# PLT-01-RevC.net
KiCad netlist of a schematic drawn in EAGLE
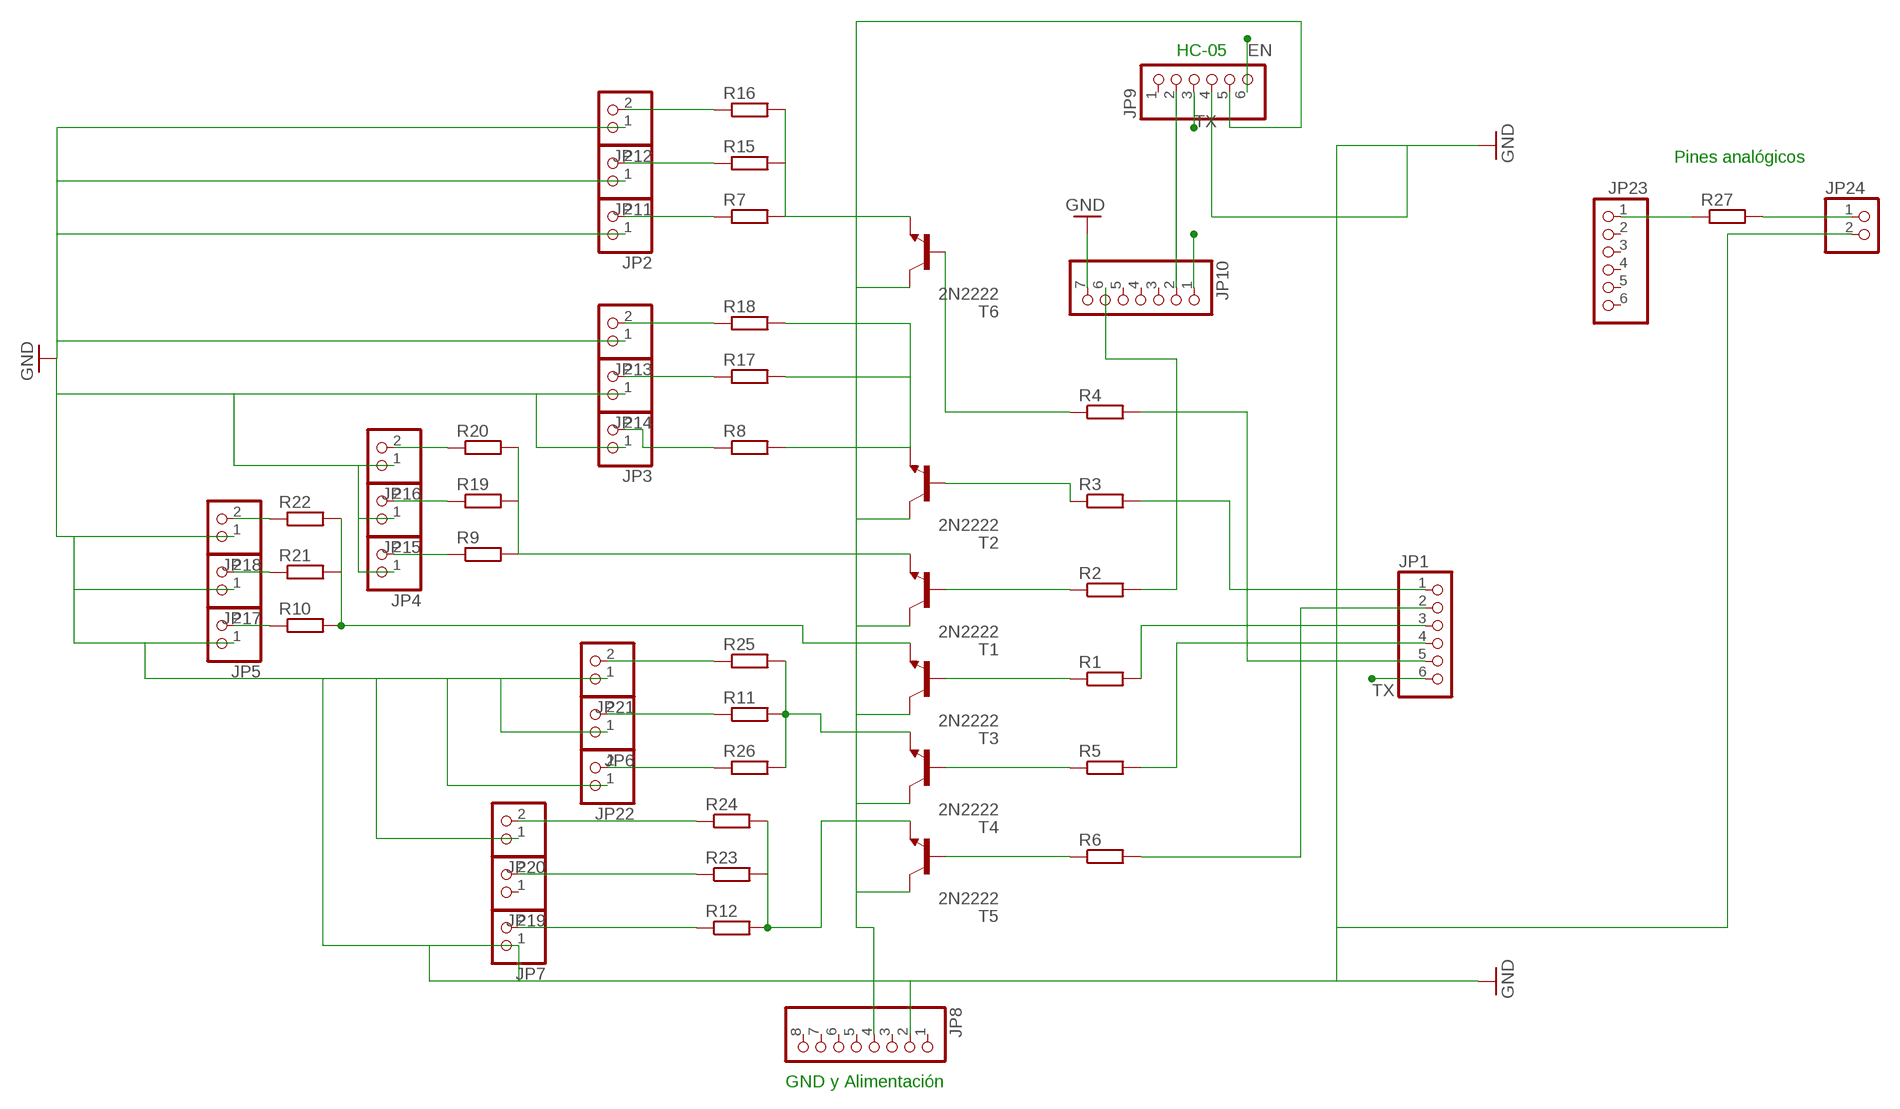
[diagram p0: schematic, sheet 1]

(export (version "E")
  (design (tool "Eeschema 10.0.6"))
  (components
    (comp (ref "JP1")
      (value "PINHD-1X6")
      (footprint "eagle-import:1X06")
      (libsource (lib "eagle-import") (part "PINHD-1X6"))
    )
    (comp (ref "JP2")
      (value "PINHD-1X2")
      (footprint "eagle-import:1X02")
      (libsource (lib "eagle-import") (part "PINHD-1X2"))
    )
    (comp (ref "JP3")
      (value "PINHD-1X2")
      (footprint "eagle-import:1X02")
      (libsource (lib "eagle-import") (part "PINHD-1X2"))
    )
    (comp (ref "JP4")
      (value "PINHD-1X2")
      (footprint "eagle-import:1X02")
      (libsource (lib "eagle-import") (part "PINHD-1X2"))
    )
    (comp (ref "JP5")
      (value "PINHD-1X2")
      (footprint "eagle-import:1X02")
      (libsource (lib "eagle-import") (part "PINHD-1X2"))
    )
    (comp (ref "JP6")
      (value "PINHD-1X2")
      (footprint "eagle-import:1X02")
      (libsource (lib "eagle-import") (part "PINHD-1X2"))
    )
    (comp (ref "JP7")
      (value "PINHD-1X2")
      (footprint "eagle-import:1X02")
      (libsource (lib "eagle-import") (part "PINHD-1X2"))
    )
    (comp (ref "JP8")
      (value "PINHD-1X8")
      (footprint "eagle-import:1X08")
      (libsource (lib "eagle-import") (part "PINHD-1X8"))
    )
    (comp (ref "JP9")
      (value "PINHD-1X6")
      (footprint "eagle-import:1X06")
      (libsource (lib "eagle-import") (part "PINHD-1X6"))
    )
    (comp (ref "JP10")
      (value "PINHD-1X7")
      (footprint "eagle-import:1X07")
      (libsource (lib "eagle-import") (part "PINHD-1X7"))
    )
    (comp (ref "JP11")
      (value "PINHD-1X2")
      (footprint "eagle-import:1X02")
      (libsource (lib "eagle-import") (part "PINHD-1X2"))
    )
    (comp (ref "JP12")
      (value "PINHD-1X2")
      (footprint "eagle-import:1X02")
      (libsource (lib "eagle-import") (part "PINHD-1X2"))
    )
    (comp (ref "JP13")
      (value "PINHD-1X2")
      (footprint "eagle-import:1X02")
      (libsource (lib "eagle-import") (part "PINHD-1X2"))
    )
    (comp (ref "JP14")
      (value "PINHD-1X2")
      (footprint "eagle-import:1X02")
      (libsource (lib "eagle-import") (part "PINHD-1X2"))
    )
    (comp (ref "JP15")
      (value "PINHD-1X2")
      (footprint "eagle-import:1X02")
      (libsource (lib "eagle-import") (part "PINHD-1X2"))
    )
    (comp (ref "JP16")
      (value "PINHD-1X2")
      (footprint "eagle-import:1X02")
      (libsource (lib "eagle-import") (part "PINHD-1X2"))
    )
    (comp (ref "JP17")
      (value "PINHD-1X2")
      (footprint "eagle-import:1X02")
      (libsource (lib "eagle-import") (part "PINHD-1X2"))
    )
    (comp (ref "JP18")
      (value "PINHD-1X2")
      (footprint "eagle-import:1X02")
      (libsource (lib "eagle-import") (part "PINHD-1X2"))
    )
    (comp (ref "JP19")
      (value "PINHD-1X2")
      (footprint "eagle-import:1X02")
      (libsource (lib "eagle-import") (part "PINHD-1X2"))
    )
    (comp (ref "JP20")
      (value "PINHD-1X2")
      (footprint "eagle-import:1X02")
      (libsource (lib "eagle-import") (part "PINHD-1X2"))
    )
    (comp (ref "JP21")
      (value "PINHD-1X2")
      (footprint "eagle-import:1X02")
      (libsource (lib "eagle-import") (part "PINHD-1X2"))
    )
    (comp (ref "JP22")
      (value "PINHD-1X2")
      (footprint "eagle-import:1X02")
      (libsource (lib "eagle-import") (part "PINHD-1X2"))
    )
    (comp (ref "JP23")
      (value "PINHD-1X6")
      (footprint "eagle-import:1X06")
      (libsource (lib "eagle-import") (part "PINHD-1X6"))
    )
    (comp (ref "JP24")
      (value "PINHD-1X2")
      (footprint "eagle-import:1X02")
      (libsource (lib "eagle-import") (part "PINHD-1X2"))
    )
    (comp (ref "R1")
      (value "R-EU_0207/10")
      (footprint "eagle-import:0207_10")
      (libsource (lib "eagle-import") (part "R-EU_0207/10"))
    )
    (comp (ref "R2")
      (value "R-EU_0207/10")
      (footprint "eagle-import:0207_10")
      (libsource (lib "eagle-import") (part "R-EU_0207/10"))
    )
    (comp (ref "R3")
      (value "R-EU_0207/10")
      (footprint "eagle-import:0207_10")
      (libsource (lib "eagle-import") (part "R-EU_0207/10"))
    )
    (comp (ref "R4")
      (value "R-EU_0207/10")
      (footprint "eagle-import:0207_10")
      (libsource (lib "eagle-import") (part "R-EU_0207/10"))
    )
    (comp (ref "R5")
      (value "R-EU_0207/10")
      (footprint "eagle-import:0207_10")
      (libsource (lib "eagle-import") (part "R-EU_0207/10"))
    )
    (comp (ref "R6")
      (value "R-EU_0207/10")
      (footprint "eagle-import:0207_10")
      (libsource (lib "eagle-import") (part "R-EU_0207/10"))
    )
    (comp (ref "R7")
      (value "R-EU_0207/10")
      (footprint "eagle-import:0207_10")
      (libsource (lib "eagle-import") (part "R-EU_0207/10"))
    )
    (comp (ref "R8")
      (value "R-EU_0207/10")
      (footprint "eagle-import:0207_10")
      (libsource (lib "eagle-import") (part "R-EU_0207/10"))
    )
    (comp (ref "R9")
      (value "R-EU_0207/10")
      (footprint "eagle-import:0207_10")
      (libsource (lib "eagle-import") (part "R-EU_0207/10"))
    )
    (comp (ref "R10")
      (value "R-EU_0207/10")
      (footprint "eagle-import:0207_10")
      (libsource (lib "eagle-import") (part "R-EU_0207/10"))
    )
    (comp (ref "R11")
      (value "R-EU_0207/10")
      (footprint "eagle-import:0207_10")
      (libsource (lib "eagle-import") (part "R-EU_0207/10"))
    )
    (comp (ref "R12")
      (value "R-EU_0207/10")
      (footprint "eagle-import:0207_10")
      (libsource (lib "eagle-import") (part "R-EU_0207/10"))
    )
    (comp (ref "R15")
      (value "R-EU_0207/10")
      (footprint "eagle-import:0207_10")
      (libsource (lib "eagle-import") (part "R-EU_0207/10"))
    )
    (comp (ref "R16")
      (value "R-EU_0207/10")
      (footprint "eagle-import:0207_10")
      (libsource (lib "eagle-import") (part "R-EU_0207/10"))
    )
    (comp (ref "R17")
      (value "R-EU_0207/10")
      (footprint "eagle-import:0207_10")
      (libsource (lib "eagle-import") (part "R-EU_0207/10"))
    )
    (comp (ref "R18")
      (value "R-EU_0207/10")
      (footprint "eagle-import:0207_10")
      (libsource (lib "eagle-import") (part "R-EU_0207/10"))
    )
    (comp (ref "R19")
      (value "R-EU_0207/10")
      (footprint "eagle-import:0207_10")
      (libsource (lib "eagle-import") (part "R-EU_0207/10"))
    )
    (comp (ref "R20")
      (value "R-EU_0207/10")
      (footprint "eagle-import:0207_10")
      (libsource (lib "eagle-import") (part "R-EU_0207/10"))
    )
    (comp (ref "R21")
      (value "R-EU_0207/10")
      (footprint "eagle-import:0207_10")
      (libsource (lib "eagle-import") (part "R-EU_0207/10"))
    )
    (comp (ref "R22")
      (value "R-EU_0207/10")
      (footprint "eagle-import:0207_10")
      (libsource (lib "eagle-import") (part "R-EU_0207/10"))
    )
    (comp (ref "R23")
      (value "R-EU_0207/10")
      (footprint "eagle-import:0207_10")
      (libsource (lib "eagle-import") (part "R-EU_0207/10"))
    )
    (comp (ref "R24")
      (value "R-EU_0207/10")
      (footprint "eagle-import:0207_10")
      (libsource (lib "eagle-import") (part "R-EU_0207/10"))
    )
    (comp (ref "R25")
      (value "R-EU_0207/10")
      (footprint "eagle-import:0207_10")
      (libsource (lib "eagle-import") (part "R-EU_0207/10"))
    )
    (comp (ref "R26")
      (value "R-EU_0207/10")
      (footprint "eagle-import:0207_10")
      (libsource (lib "eagle-import") (part "R-EU_0207/10"))
    )
    (comp (ref "R27")
      (value "R-EU_0207/10")
      (footprint "eagle-import:0207_10")
      (libsource (lib "eagle-import") (part "R-EU_0207/10"))
    )
    (comp (ref "T1")
      (value "2N2222")
      (footprint "eagle-import:TO92-EBC-OVAL")
      (libsource (lib "eagle-import") (part "2N2222"))
    )
    (comp (ref "T2")
      (value "2N2222")
      (footprint "eagle-import:TO92-EBC-OVAL")
      (libsource (lib "eagle-import") (part "2N2222"))
    )
    (comp (ref "T3")
      (value "2N2222")
      (footprint "eagle-import:TO92-EBC-OVAL")
      (libsource (lib "eagle-import") (part "2N2222"))
    )
    (comp (ref "T4")
      (value "2N2222")
      (footprint "eagle-import:TO92-EBC-OVAL")
      (libsource (lib "eagle-import") (part "2N2222"))
    )
    (comp (ref "T5")
      (value "2N2222")
      (footprint "eagle-import:TO92-EBC-OVAL")
      (libsource (lib "eagle-import") (part "2N2222"))
    )
    (comp (ref "T6")
      (value "2N2222")
      (footprint "eagle-import:TO92-EBC-OVAL")
      (libsource (lib "eagle-import") (part "2N2222"))
    )
  )
  (nets
    (net (code "1") (name "/EN") (class "Default")
      (node (ref "JP10") (pin "1") (pinfunction "1_1") (pintype "passive"))
      (node (ref "JP9") (pin "6") (pinfunction "6_6") (pintype "passive"))
    )
    (net (code "2") (name "/TX") (class "Default")
      (node (ref "JP1") (pin "6") (pinfunction "6_6") (pintype "passive"))
      (node (ref "JP9") (pin "3") (pinfunction "3_3") (pintype "passive"))
    )
    (net (code "3") (name "GND") (class "Default")
      (node (ref "JP10") (pin "7") (pinfunction "7_7") (pintype "passive"))
      (node (ref "JP11") (pin "1") (pinfunction "1_1") (pintype "passive"))
      (node (ref "JP12") (pin "1") (pinfunction "1_1") (pintype "passive"))
      (node (ref "JP13") (pin "1") (pinfunction "1_1") (pintype "passive"))
      (node (ref "JP14") (pin "1") (pinfunction "1_1") (pintype "passive"))
      (node (ref "JP15") (pin "1") (pinfunction "1_1") (pintype "passive"))
      (node (ref "JP16") (pin "1") (pinfunction "1_1") (pintype "passive"))
      (node (ref "JP17") (pin "1") (pinfunction "1_1") (pintype "passive"))
      (node (ref "JP18") (pin "1") (pinfunction "1_1") (pintype "passive"))
      (node (ref "JP2") (pin "1") (pinfunction "1_1") (pintype "passive"))
      (node (ref "JP20") (pin "1") (pinfunction "1_1") (pintype "passive"))
      (node (ref "JP21") (pin "1") (pinfunction "1_1") (pintype "passive"))
      (node (ref "JP22") (pin "1") (pinfunction "1_1") (pintype "passive"))
      (node (ref "JP24") (pin "2") (pinfunction "2_2") (pintype "passive"))
      (node (ref "JP3") (pin "1") (pinfunction "1_1") (pintype "passive"))
      (node (ref "JP4") (pin "1") (pinfunction "1_1") (pintype "passive"))
      (node (ref "JP5") (pin "1") (pinfunction "1_1") (pintype "passive"))
      (node (ref "JP6") (pin "1") (pinfunction "1_1") (pintype "passive"))
      (node (ref "JP7") (pin "1") (pinfunction "1_1") (pintype "passive"))
      (node (ref "JP8") (pin "2") (pinfunction "2_2") (pintype "passive"))
      (node (ref "JP9") (pin "4") (pinfunction "4_4") (pintype "passive"))
    )
    (net (code "4") (name "Net-(JP1-Pad1)") (class "Default")
      (node (ref "JP1") (pin "1") (pinfunction "1_1") (pintype "passive"))
      (node (ref "R3") (pin "2") (pinfunction "2_2") (pintype "passive"))
    )
    (net (code "5") (name "Net-(JP1-Pad2)") (class "Default")
      (node (ref "JP1") (pin "2") (pinfunction "2_2") (pintype "passive"))
      (node (ref "R6") (pin "2") (pinfunction "2_2") (pintype "passive"))
    )
    (net (code "6") (name "Net-(JP1-Pad3)") (class "Default")
      (node (ref "JP1") (pin "3") (pinfunction "3_3") (pintype "passive"))
      (node (ref "R1") (pin "2") (pinfunction "2_2") (pintype "passive"))
    )
    (net (code "7") (name "Net-(JP1-Pad4)") (class "Default")
      (node (ref "JP1") (pin "4") (pinfunction "4_4") (pintype "passive"))
      (node (ref "R5") (pin "2") (pinfunction "2_2") (pintype "passive"))
    )
    (net (code "8") (name "Net-(JP1-Pad5)") (class "Default")
      (node (ref "JP1") (pin "5") (pinfunction "5_5") (pintype "passive"))
      (node (ref "R4") (pin "2") (pinfunction "2_2") (pintype "passive"))
    )
    (net (code "9") (name "Net-(JP2-Pad2)") (class "Default")
      (node (ref "JP2") (pin "2") (pinfunction "2_2") (pintype "passive"))
      (node (ref "R7") (pin "1") (pinfunction "1_1") (pintype "passive"))
    )
    (net (code "10") (name "Net-(JP3-Pad2)") (class "Default")
      (node (ref "JP3") (pin "2") (pinfunction "2_2") (pintype "passive"))
      (node (ref "R8") (pin "1") (pinfunction "1_1") (pintype "passive"))
    )
    (net (code "11") (name "Net-(JP4-Pad2)") (class "Default")
      (node (ref "JP4") (pin "2") (pinfunction "2_2") (pintype "passive"))
      (node (ref "R9") (pin "1") (pinfunction "1_1") (pintype "passive"))
    )
    (net (code "12") (name "Net-(JP5-Pad2)") (class "Default")
      (node (ref "JP5") (pin "2") (pinfunction "2_2") (pintype "passive"))
      (node (ref "R10") (pin "1") (pinfunction "1_1") (pintype "passive"))
    )
    (net (code "13") (name "Net-(JP6-Pad2)") (class "Default")
      (node (ref "JP6") (pin "2") (pinfunction "2_2") (pintype "passive"))
      (node (ref "R11") (pin "1") (pinfunction "1_1") (pintype "passive"))
    )
    (net (code "14") (name "Net-(JP7-Pad2)") (class "Default")
      (node (ref "JP7") (pin "2") (pinfunction "2_2") (pintype "passive"))
      (node (ref "R12") (pin "1") (pinfunction "1_1") (pintype "passive"))
    )
    (net (code "15") (name "Net-(JP8-Pad4)") (class "Default")
      (node (ref "JP8") (pin "4") (pinfunction "4_4") (pintype "passive"))
      (node (ref "JP9") (pin "5") (pinfunction "5_5") (pintype "passive"))
      (node (ref "T1") (pin "C") (pinfunction "C_C") (pintype "passive"))
      (node (ref "T2") (pin "C") (pinfunction "C_C") (pintype "passive"))
      (node (ref "T3") (pin "C") (pinfunction "C_C") (pintype "passive"))
      (node (ref "T4") (pin "C") (pinfunction "C_C") (pintype "passive"))
      (node (ref "T5") (pin "C") (pinfunction "C_C") (pintype "passive"))
      (node (ref "T6") (pin "C") (pinfunction "C_C") (pintype "passive"))
    )
    (net (code "16") (name "Net-(JP10-Pad2)") (class "Default")
      (node (ref "JP10") (pin "2") (pinfunction "2_2") (pintype "passive"))
      (node (ref "JP9") (pin "2") (pinfunction "2_2") (pintype "passive"))
    )
    (net (code "17") (name "Net-(JP10-Pad6)") (class "Default")
      (node (ref "JP10") (pin "6") (pinfunction "6_6") (pintype "passive"))
      (node (ref "R2") (pin "2") (pinfunction "2_2") (pintype "passive"))
    )
    (net (code "18") (name "Net-(JP11-Pad2)") (class "Default")
      (node (ref "JP11") (pin "2") (pinfunction "2_2") (pintype "passive"))
      (node (ref "R15") (pin "1") (pinfunction "1_1") (pintype "passive"))
    )
    (net (code "19") (name "Net-(JP12-Pad2)") (class "Default")
      (node (ref "JP12") (pin "2") (pinfunction "2_2") (pintype "passive"))
      (node (ref "R16") (pin "1") (pinfunction "1_1") (pintype "passive"))
    )
    (net (code "20") (name "Net-(JP13-Pad2)") (class "Default")
      (node (ref "JP13") (pin "2") (pinfunction "2_2") (pintype "passive"))
      (node (ref "R18") (pin "1") (pinfunction "1_1") (pintype "passive"))
    )
    (net (code "21") (name "Net-(JP14-Pad2)") (class "Default")
      (node (ref "JP14") (pin "2") (pinfunction "2_2") (pintype "passive"))
      (node (ref "R17") (pin "1") (pinfunction "1_1") (pintype "passive"))
    )
    (net (code "22") (name "Net-(JP15-Pad2)") (class "Default")
      (node (ref "JP15") (pin "2") (pinfunction "2_2") (pintype "passive"))
      (node (ref "R19") (pin "1") (pinfunction "1_1") (pintype "passive"))
    )
    (net (code "23") (name "Net-(JP16-Pad2)") (class "Default")
      (node (ref "JP16") (pin "2") (pinfunction "2_2") (pintype "passive"))
      (node (ref "R20") (pin "1") (pinfunction "1_1") (pintype "passive"))
    )
    (net (code "24") (name "Net-(JP17-Pad2)") (class "Default")
      (node (ref "JP17") (pin "2") (pinfunction "2_2") (pintype "passive"))
      (node (ref "R21") (pin "1") (pinfunction "1_1") (pintype "passive"))
    )
    (net (code "25") (name "Net-(JP18-Pad2)") (class "Default")
      (node (ref "JP18") (pin "2") (pinfunction "2_2") (pintype "passive"))
      (node (ref "R22") (pin "1") (pinfunction "1_1") (pintype "passive"))
    )
    (net (code "26") (name "Net-(JP19-Pad2)") (class "Default")
      (node (ref "JP19") (pin "2") (pinfunction "2_2") (pintype "passive"))
      (node (ref "R23") (pin "1") (pinfunction "1_1") (pintype "passive"))
    )
    (net (code "27") (name "Net-(JP20-Pad2)") (class "Default")
      (node (ref "JP20") (pin "2") (pinfunction "2_2") (pintype "passive"))
      (node (ref "R24") (pin "1") (pinfunction "1_1") (pintype "passive"))
    )
    (net (code "28") (name "Net-(JP21-Pad2)") (class "Default")
      (node (ref "JP21") (pin "2") (pinfunction "2_2") (pintype "passive"))
      (node (ref "R25") (pin "1") (pinfunction "1_1") (pintype "passive"))
    )
    (net (code "29") (name "Net-(JP22-Pad2)") (class "Default")
      (node (ref "JP22") (pin "2") (pinfunction "2_2") (pintype "passive"))
      (node (ref "R26") (pin "1") (pinfunction "1_1") (pintype "passive"))
    )
    (net (code "30") (name "Net-(JP23-Pad1)") (class "Default")
      (node (ref "JP23") (pin "1") (pinfunction "1_1") (pintype "passive"))
      (node (ref "R27") (pin "1") (pinfunction "1_1") (pintype "passive"))
    )
    (net (code "31") (name "Net-(JP24-Pad1)") (class "Default")
      (node (ref "JP24") (pin "1") (pinfunction "1_1") (pintype "passive"))
      (node (ref "R27") (pin "2") (pinfunction "2_2") (pintype "passive"))
    )
    (net (code "32") (name "Net-(R1-Pad1)") (class "Default")
      (node (ref "R1") (pin "1") (pinfunction "1_1") (pintype "passive"))
      (node (ref "T3") (pin "B") (pinfunction "B_B") (pintype "passive"))
    )
    (net (code "33") (name "Net-(R2-Pad1)") (class "Default")
      (node (ref "R2") (pin "1") (pinfunction "1_1") (pintype "passive"))
      (node (ref "T1") (pin "B") (pinfunction "B_B") (pintype "passive"))
    )
    (net (code "34") (name "Net-(R3-Pad1)") (class "Default")
      (node (ref "R3") (pin "1") (pinfunction "1_1") (pintype "passive"))
      (node (ref "T2") (pin "B") (pinfunction "B_B") (pintype "passive"))
    )
    (net (code "35") (name "Net-(R4-Pad1)") (class "Default")
      (node (ref "R4") (pin "1") (pinfunction "1_1") (pintype "passive"))
      (node (ref "T6") (pin "B") (pinfunction "B_B") (pintype "passive"))
    )
    (net (code "36") (name "Net-(R5-Pad1)") (class "Default")
      (node (ref "R5") (pin "1") (pinfunction "1_1") (pintype "passive"))
      (node (ref "T4") (pin "B") (pinfunction "B_B") (pintype "passive"))
    )
    (net (code "37") (name "Net-(R6-Pad1)") (class "Default")
      (node (ref "R6") (pin "1") (pinfunction "1_1") (pintype "passive"))
      (node (ref "T5") (pin "B") (pinfunction "B_B") (pintype "passive"))
    )
    (net (code "38") (name "Net-(R10-Pad2)") (class "Default")
      (node (ref "R10") (pin "2") (pinfunction "2_2") (pintype "passive"))
      (node (ref "R21") (pin "2") (pinfunction "2_2") (pintype "passive"))
      (node (ref "R22") (pin "2") (pinfunction "2_2") (pintype "passive"))
      (node (ref "T3") (pin "E") (pinfunction "E_E") (pintype "passive"))
    )
    (net (code "39") (name "Net-(R11-Pad2)") (class "Default")
      (node (ref "R11") (pin "2") (pinfunction "2_2") (pintype "passive"))
      (node (ref "R25") (pin "2") (pinfunction "2_2") (pintype "passive"))
      (node (ref "R26") (pin "2") (pinfunction "2_2") (pintype "passive"))
      (node (ref "T4") (pin "E") (pinfunction "E_E") (pintype "passive"))
    )
    (net (code "40") (name "Net-(R12-Pad2)") (class "Default")
      (node (ref "R12") (pin "2") (pinfunction "2_2") (pintype "passive"))
      (node (ref "R23") (pin "2") (pinfunction "2_2") (pintype "passive"))
      (node (ref "R24") (pin "2") (pinfunction "2_2") (pintype "passive"))
      (node (ref "T5") (pin "E") (pinfunction "E_E") (pintype "passive"))
    )
    (net (code "41") (name "Net-(R15-Pad2)") (class "Default")
      (node (ref "R15") (pin "2") (pinfunction "2_2") (pintype "passive"))
      (node (ref "R16") (pin "2") (pinfunction "2_2") (pintype "passive"))
      (node (ref "R7") (pin "2") (pinfunction "2_2") (pintype "passive"))
      (node (ref "T6") (pin "E") (pinfunction "E_E") (pintype "passive"))
    )
    (net (code "42") (name "Net-(R17-Pad2)") (class "Default")
      (node (ref "R17") (pin "2") (pinfunction "2_2") (pintype "passive"))
      (node (ref "R18") (pin "2") (pinfunction "2_2") (pintype "passive"))
      (node (ref "R8") (pin "2") (pinfunction "2_2") (pintype "passive"))
      (node (ref "T2") (pin "E") (pinfunction "E_E") (pintype "passive"))
    )
    (net (code "43") (name "Net-(R19-Pad2)") (class "Default")
      (node (ref "R19") (pin "2") (pinfunction "2_2") (pintype "passive"))
      (node (ref "R20") (pin "2") (pinfunction "2_2") (pintype "passive"))
      (node (ref "R9") (pin "2") (pinfunction "2_2") (pintype "passive"))
      (node (ref "T1") (pin "E") (pinfunction "E_E") (pintype "passive"))
    )
    (net (code "44") (name "unconnected-(JP8-Pad1)") (class "Default")
      (node (ref "JP8") (pin "1") (pinfunction "1_1") (pintype "passive"))
    )
    (net (code "45") (name "unconnected-(JP8-Pad3)") (class "Default")
      (node (ref "JP8") (pin "3") (pinfunction "3_3") (pintype "passive"))
    )
    (net (code "46") (name "unconnected-(JP8-Pad5)") (class "Default")
      (node (ref "JP8") (pin "5") (pinfunction "5_5") (pintype "passive"))
    )
    (net (code "47") (name "unconnected-(JP8-Pad6)") (class "Default")
      (node (ref "JP8") (pin "6") (pinfunction "6_6") (pintype "passive"))
    )
    (net (code "48") (name "unconnected-(JP8-Pad7)") (class "Default")
      (node (ref "JP8") (pin "7") (pinfunction "7_7") (pintype "passive"))
    )
    (net (code "49") (name "unconnected-(JP8-Pad8)") (class "Default")
      (node (ref "JP8") (pin "8") (pinfunction "8_8") (pintype "passive"))
    )
    (net (code "50") (name "unconnected-(JP9-Pad1)") (class "Default")
      (node (ref "JP9") (pin "1") (pinfunction "1_1") (pintype "passive"))
    )
    (net (code "51") (name "unconnected-(JP10-Pad3)") (class "Default")
      (node (ref "JP10") (pin "3") (pinfunction "3_3") (pintype "passive"))
    )
    (net (code "52") (name "unconnected-(JP10-Pad4)") (class "Default")
      (node (ref "JP10") (pin "4") (pinfunction "4_4") (pintype "passive"))
    )
    (net (code "53") (name "unconnected-(JP10-Pad5)") (class "Default")
      (node (ref "JP10") (pin "5") (pinfunction "5_5") (pintype "passive"))
    )
    (net (code "54") (name "unconnected-(JP19-Pad1)") (class "Default")
      (node (ref "JP19") (pin "1") (pinfunction "1_1") (pintype "passive"))
    )
    (net (code "55") (name "unconnected-(JP23-Pad2)") (class "Default")
      (node (ref "JP23") (pin "2") (pinfunction "2_2") (pintype "passive"))
    )
    (net (code "56") (name "unconnected-(JP23-Pad3)") (class "Default")
      (node (ref "JP23") (pin "3") (pinfunction "3_3") (pintype "passive"))
    )
    (net (code "57") (name "unconnected-(JP23-Pad4)") (class "Default")
      (node (ref "JP23") (pin "4") (pinfunction "4_4") (pintype "passive"))
    )
    (net (code "58") (name "unconnected-(JP23-Pad5)") (class "Default")
      (node (ref "JP23") (pin "5") (pinfunction "5_5") (pintype "passive"))
    )
    (net (code "59") (name "unconnected-(JP23-Pad6)") (class "Default")
      (node (ref "JP23") (pin "6") (pinfunction "6_6") (pintype "passive"))
    )
  )
)
